# 3V3.net
KiCad netlist of a schematic drawn in Altium Designer
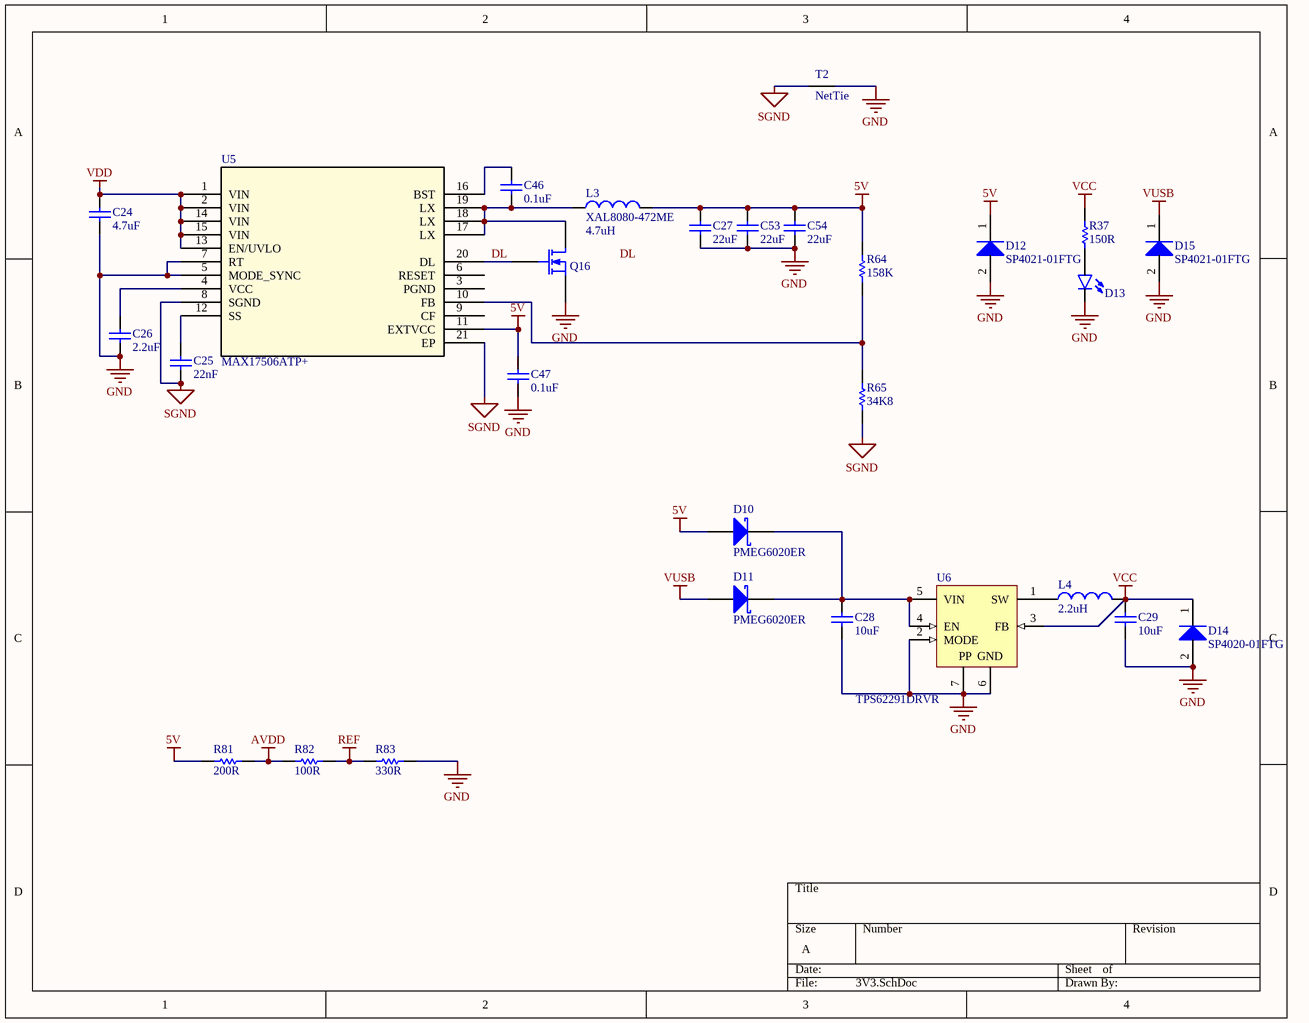
[diagram p0: 3V3.SchDoc]

(export (version "E")
  (design (tool "Eeschema 10.0.6"))
  (components
    (comp (ref "C24")
      (value "4.7uF")
      (footprint "C1210[3225X200]")
      (description "4.7uF 100V 10% 1210 (3225 Metric)")
      (fields (field (name "PARTNUMBER") "GRJ32DC72A475KE11L") (field (name "MANUFACTURER") "Murata"))
      (libsource (lib "Capacitors") (part "CAP_4.7uF_100V_1210_10%"))
    )
    (comp (ref "C25")
      (value "22nF")
      (footprint "C0603[1608X92]")
      (description "22nF 50V 10% 0603 (1608 Metric)")
      (fields (field (name "PARTNUMBER") "GRM188R71H223KA01D") (field (name "MANUFACTURER") "Murata"))
      (libsource (lib "Capacitors") (part "CAP_22nF_50V_0603_10%"))
    )
    (comp (ref "C26")
      (value "2.2uF")
      (footprint "C0603[1608X92]")
      (description "2.2uF 10V 10% 0603 (1608 Metric)")
      (fields (field (name "PARTNUMBER") "GRT188R61A225KE13D") (field (name "MANUFACTURER") "Murata"))
      (libsource (lib "Capacitors") (part "CAP_2.2uF_10V_0603_10%"))
    )
    (comp (ref "C27")
      (value "22uF")
      (footprint "C1210[3225X250]")
      (description "22uF 16V 20% 1210 (3225 Metric)")
      (fields (field (name "PARTNUMBER") "GRM32ER61C476ME15L") (field (name "MANUFACTURER") "Murata"))
      (libsource (lib "Capacitors") (part "CAP_22uF_16V_1210_20%_1"))
    )
    (comp (ref "C28")
      (value "10uF")
      (footprint "C0603[1608X92]")
      (description "10uF 16V 10% 0603 (1608 Metric)")
      (fields (field (name "PARTNUMBER") "GRM188R61C106KAALD") (field (name "MANUFACTURER") "Murata"))
      (libsource (lib "Capacitors") (part "CAP_10uF_16V_0603_10%"))
    )
    (comp (ref "C29")
      (value "10uF")
      (footprint "C0603[1608X92]")
      (description "10uF 6.3V 10% 0603 (1608 Metric)")
      (fields (field (name "PARTNUMBER") "GRM188R60J106KE47D") (field (name "MANUFACTURER") "Murata"))
      (libsource (lib "Capacitors") (part "CAP_10uF_6.3V_0603_10%"))
    )
    (comp (ref "C46")
      (value "0.1uF")
      (footprint "C0603[1608X92]")
      (description "0.1uF 16V 10% 0603 (1608 Metric)")
      (fields (field (name "PARTNUMBER") "GCM188R71C104KA37D") (field (name "MANUFACTURER") "Murata"))
      (libsource (lib "Capacitors") (part "CAP_0.1uF_16V_0603_10%"))
    )
    (comp (ref "C47")
      (value "0.1uF")
      (footprint "C0603[1608X92]")
      (description "0.1uF 6.3V 10% 0603 (1608 Metric)")
      (fields (field (name "PARTNUMBER") "GRM188R70J104KA01D") (field (name "MANUFACTURER") "Murata"))
      (libsource (lib "Capacitors") (part "CAP_0.1uF_6.3V_0603_10%"))
    )
    (comp (ref "C53")
      (value "22uF")
      (footprint "C1210[3225X250]")
      (description "22uF 16V 20% 1210 (3225 Metric)")
      (fields (field (name "PARTNUMBER") "GRM32ER61C476ME15L") (field (name "MANUFACTURER") "Murata"))
      (libsource (lib "Capacitors") (part "CAP_22uF_16V_1210_20%_1"))
    )
    (comp (ref "C54")
      (value "22uF")
      (footprint "C1210[3225X250]")
      (description "22uF 16V 20% 1210 (3225 Metric)")
      (fields (field (name "PARTNUMBER") "GRM32ER61C476ME15L") (field (name "MANUFACTURER") "Murata"))
      (libsource (lib "Capacitors") (part "CAP_22uF_16V_1210_20%_1"))
    )
    (comp (ref "D10")
      (value "PMEG6020ER")
      (footprint "SOD-123")
      (fields (field (name "PARTNUMBER") "PMEG6020ER,115") (field (name "MANUFACTURER") "NXP Semiconductors"))
      (libsource (lib "Diodes") (part "PMEG6020ER"))
    )
    (comp (ref "D11")
      (value "PMEG6020ER")
      (footprint "SOD-123")
      (fields (field (name "PARTNUMBER") "PMEG6020ER,115") (field (name "MANUFACTURER") "NXP Semiconductors"))
      (libsource (lib "Diodes") (part "PMEG6020ER"))
    )
    (comp (ref "D12")
      (value "SP4021-01FTG")
      (footprint "SOD-323")
      (fields (field (name "MANUFACTURER") "Littelfuse"))
      (libsource (lib "Diodes") (part "SP4021-01FTG"))
    )
    (comp (ref "D13")
      (value "LED_0603_GREEN_5mA")
      (footprint "LED0603")
      (fields (field (name "PARTNUMBER") "LTST-C193TGKT-5A") (field (name "MANUFACTURER") "Lite-On Inc."))
      (libsource (lib "LEDs") (part "LED_0603_GREEN_5mA"))
    )
    (comp (ref "D14")
      (value "SP4020-01FTG")
      (footprint "SOD-323")
      (fields (field (name "MANUFACTURER") "Littelfuse"))
      (libsource (lib "Diodes") (part "SP4020-01FTG"))
    )
    (comp (ref "D15")
      (value "SP4021-01FTG")
      (footprint "SOD-323")
      (fields (field (name "MANUFACTURER") "Littelfuse"))
      (libsource (lib "Diodes-TVS") (part "SP4021-01FTG"))
    )
    (comp (ref "L3")
      (value "XAL8080-472ME")
      (footprint "XAL8080")
      (description "4.7uH 38A 4.08mOhms")
      (fields
        (field (name "ALTIUM_VALUE") "4.7uH")
        (field (name "PARTNUMBER") "XAL8080-472MED")
        (field (name "MANUFACTURER") "Coilcraft")
        (field (name "PUBLISHER") "Altium Limited")
      )
      (libsource (lib "General_Component") (part "XAL8080-472ME"))
    )
    (comp (ref "L4")
      (value "2.2uH")
      (footprint "IND0805")
      (description "2.2uH 20% 1.7A 0805")
      (fields (field (name "PARTNUMBER") "LQM21PN2R2MGHL") (field (name "MANUFACTURER") "Murata"))
      (libsource (lib "Inductors") (part "IND_2.2uH_1.7A_0805_20%"))
    )
    (comp (ref "Q16")
      (value "SIS862DN-T1-GE3")
      (footprint "PowerPak-1212-8")
      (description "N-Channel MOSFET")
      (fields (field (name "MANUFACTURER") "Vishay"))
      (libsource (lib "MOSFETs") (part "SIS862DN-T1-GE3"))
    )
    (comp (ref "R37")
      (value "150R")
      (footprint "R0603[1608]")
      (description "150R 0.25W 1% 0603 (1005 Metric)")
      (fields (field (name "MANUFACTURER") "Vishay / Dale") (field (name "PARTNUMBER") "CRCW0603150RFKEAHP"))
      (libsource (lib "Resistors") (part "RES_150R_0603_1%"))
    )
    (comp (ref "R64")
      (value "158K")
      (footprint "R0603[1608]")
      (description "158K 0.25W 1% 0603 (1005 Metric)")
      (fields (field (name "MANUFACTURER") "Vishay / Dale") (field (name "PARTNUMBER") "CRCW0603158KFKEAHP"))
      (libsource (lib "Resistors") (part "RES_158K_0603_1%"))
    )
    (comp (ref "R65")
      (value "34K8")
      (footprint "R0603[1608]")
      (description "34K8 0.25W 1% 0603 (1005 Metric)")
      (fields (field (name "MANUFACTURER") "Vishay / Dale") (field (name "PARTNUMBER") "CRCW060334K8FKEAHP"))
      (libsource (lib "Resistors") (part "RES_34K8_0603_1%"))
    )
    (comp (ref "R81")
      (value "200R")
      (footprint "R0603[1608]")
      (description "200R 0.25W 1% 0603 (1005 Metric)")
      (fields (field (name "MANUFACTURER") "Vishay / Dale") (field (name "PARTNUMBER") "CRCW0603200RFKEAHP"))
      (libsource (lib "Resistors") (part "RES_200R_0603_1%"))
    )
    (comp (ref "R82")
      (value "100R")
      (footprint "R0603[1608]")
      (description "100R 0.25W 1% 0603 (1005 Metric)")
      (fields (field (name "MANUFACTURER") "Vishay / Dale") (field (name "PARTNUMBER") "CRCW0603100RFKEAHP"))
      (libsource (lib "Resistors") (part "RES_100R_0603_1%"))
    )
    (comp (ref "R83")
      (value "330R")
      (footprint "R0603[1608]")
      (description "330R 0.25W 1% 0603 (1005 Metric)")
      (fields (field (name "MANUFACTURER") "Vishay / Dale") (field (name "PARTNUMBER") "CRCW0603330RFKEAHP"))
      (libsource (lib "Resistors") (part "RES_330R_0603_1%"))
    )
    (comp (ref "T2") (value "NetTie") (footprint "NetTie") (libsource (lib "Components") (part "NetTie")))
    (comp (ref "U5")
      (value "MAX17506ATP+")
      (footprint "21-0140L_T2055-4")
      (fields (field (name "MANUFACTURER") "Maxim"))
      (libsource (lib "General_Component") (part "MAX17506ATP+"))
    )
    (comp (ref "U6")
      (value "TPS62291DRVR")
      (footprint "WSON-6")
      (description "Voltage Regulators - Switching Regulators 2.25MHz 1A Step-Down Cnvrtr 3.3V Output")
      (fields (field (name "MANUFACTURER") "Texas Instruments"))
      (libsource (lib "ICs") (part "TPS62291DRVR"))
    )
  )
  (nets
    (net (code "1") (name "/DL") (class "Default")
      (node (ref "Q16") (pin "2") (pinfunction "G_2") (pintype "passive"))
      (node (ref "U5") (pin "20") (pinfunction "DL_20") (pintype "passive"))
    )
    (net (code "2") (name "5V") (class "Default")
      (node (ref "C27") (pin "2") (pinfunction "2_2") (pintype "passive"))
      (node (ref "C47") (pin "2") (pinfunction "2_2") (pintype "passive"))
      (node (ref "C53") (pin "2") (pinfunction "2_2") (pintype "passive"))
      (node (ref "C54") (pin "2") (pinfunction "2_2") (pintype "passive"))
      (node (ref "D10") (pin "2") (pinfunction "A_2") (pintype "passive"))
      (node (ref "D12") (pin "1") (pinfunction "K_1") (pintype "passive"))
      (node (ref "L3") (pin "2") (pinfunction "2_2") (pintype "passive"))
      (node (ref "R64") (pin "2") (pinfunction "2_2") (pintype "passive"))
      (node (ref "R81") (pin "1") (pinfunction "1_1") (pintype "passive"))
      (node (ref "U5") (pin "11") (pinfunction "EXTVCC_11") (pintype "passive"))
    )
    (net (code "3") (name "AVDD") (class "Default")
      (node (ref "R81") (pin "2") (pinfunction "2_2") (pintype "passive"))
      (node (ref "R82") (pin "1") (pinfunction "1_1") (pintype "passive"))
    )
    (net (code "4") (name "GND") (class "Default")
      (node (ref "C24") (pin "1") (pinfunction "1_1") (pintype "passive"))
      (node (ref "C26") (pin "1") (pinfunction "1_1") (pintype "passive"))
      (node (ref "C27") (pin "1") (pinfunction "1_1") (pintype "passive"))
      (node (ref "C28") (pin "1") (pinfunction "1_1") (pintype "passive"))
      (node (ref "C29") (pin "1") (pinfunction "1_1") (pintype "passive"))
      (node (ref "C47") (pin "1") (pinfunction "1_1") (pintype "passive"))
      (node (ref "C53") (pin "1") (pinfunction "1_1") (pintype "passive"))
      (node (ref "C54") (pin "1") (pinfunction "1_1") (pintype "passive"))
      (node (ref "D12") (pin "2") (pinfunction "A_2") (pintype "passive"))
      (node (ref "D13") (pin "C") (pinfunction "C_C") (pintype "passive"))
      (node (ref "D14") (pin "2") (pinfunction "A_2") (pintype "passive"))
      (node (ref "D15") (pin "2") (pinfunction "A_2") (pintype "passive"))
      (node (ref "Q16") (pin "1") (pinfunction "S_1") (pintype "passive"))
      (node (ref "R83") (pin "2") (pinfunction "2_2") (pintype "passive"))
      (node (ref "T2") (pin "2") (pinfunction "2_2") (pintype "passive"))
      (node (ref "U5") (pin "5") (pinfunction "MODE_SYNC_5") (pintype "passive"))
      (node (ref "U5") (pin "7") (pinfunction "RT_7") (pintype "passive"))
      (node (ref "U6") (pin "2") (pinfunction "MODE_2") (pintype "input"))
      (node (ref "U6") (pin "6") (pinfunction "GND_6") (pintype "power_in"))
      (node (ref "U6") (pin "7") (pinfunction "EP_7") (pintype "passive"))
    )
    (net (code "5") (name "Net-(D10-K)") (class "Default")
      (node (ref "C28") (pin "2") (pinfunction "2_2") (pintype "passive"))
      (node (ref "D10") (pin "1") (pinfunction "K_1") (pintype "passive"))
      (node (ref "D11") (pin "1") (pinfunction "K_1") (pintype "passive"))
      (node (ref "U6") (pin "4") (pinfunction "EN_4") (pintype "input"))
      (node (ref "U6") (pin "5") (pinfunction "VIN_5") (pintype "power_in"))
    )
    (net (code "6") (name "Net-(D13-PadA)") (class "Default")
      (node (ref "D13") (pin "A") (pinfunction "A_A") (pintype "passive"))
      (node (ref "R37") (pin "1") (pinfunction "1_1") (pintype "passive"))
    )
    (net (code "7") (name "Net-(Q16-D)") (class "Default")
      (node (ref "C46") (pin "1") (pinfunction "1_1") (pintype "passive"))
      (node (ref "L3") (pin "1") (pinfunction "1_1") (pintype "passive"))
      (node (ref "Q16") (pin "3") (pinfunction "D_3") (pintype "passive"))
      (node (ref "U5") (pin "17") (pinfunction "LX_17") (pintype "passive"))
      (node (ref "U5") (pin "18") (pinfunction "LX_18") (pintype "passive"))
      (node (ref "U5") (pin "19") (pinfunction "LX_19") (pintype "passive"))
    )
    (net (code "8") (name "Net-(U5-BST)") (class "Default")
      (node (ref "C46") (pin "2") (pinfunction "2_2") (pintype "passive"))
      (node (ref "U5") (pin "16") (pinfunction "BST_16") (pintype "passive"))
    )
    (net (code "9") (name "Net-(U5-FB)") (class "Default")
      (node (ref "R64") (pin "1") (pinfunction "1_1") (pintype "passive"))
      (node (ref "R65") (pin "2") (pinfunction "2_2") (pintype "passive"))
      (node (ref "U5") (pin "10") (pinfunction "FB_10") (pintype "passive"))
    )
    (net (code "10") (name "Net-(U5-SS)") (class "Default")
      (node (ref "C25") (pin "2") (pinfunction "2_2") (pintype "passive"))
      (node (ref "U5") (pin "12") (pinfunction "SS_12") (pintype "passive"))
    )
    (net (code "11") (name "Net-(U5-VCC)") (class "Default")
      (node (ref "C26") (pin "2") (pinfunction "2_2") (pintype "passive"))
      (node (ref "U5") (pin "4") (pinfunction "VCC_4") (pintype "power_in"))
    )
    (net (code "12") (name "Net-(U6-SW)") (class "Default")
      (node (ref "L4") (pin "1") (pinfunction "1_1") (pintype "passive"))
      (node (ref "U6") (pin "1") (pinfunction "SW_1") (pintype "power_in"))
    )
    (net (code "13") (name "REF") (class "Default")
      (node (ref "R82") (pin "2") (pinfunction "2_2") (pintype "passive"))
      (node (ref "R83") (pin "1") (pinfunction "1_1") (pintype "passive"))
    )
    (net (code "14") (name "SGND") (class "Default")
      (node (ref "C25") (pin "1") (pinfunction "1_1") (pintype "passive"))
      (node (ref "R65") (pin "1") (pinfunction "1_1") (pintype "passive"))
      (node (ref "T2") (pin "1") (pinfunction "1_1") (pintype "passive"))
      (node (ref "U5") (pin "21") (pinfunction "EP_21") (pintype "passive"))
      (node (ref "U5") (pin "8") (pinfunction "SGND_8") (pintype "power_in"))
    )
    (net (code "15") (name "VCC") (class "Default")
      (node (ref "C29") (pin "2") (pinfunction "2_2") (pintype "passive"))
      (node (ref "D14") (pin "1") (pinfunction "K_1") (pintype "passive"))
      (node (ref "L4") (pin "2") (pinfunction "2_2") (pintype "passive"))
      (node (ref "R37") (pin "2") (pinfunction "2_2") (pintype "passive"))
      (node (ref "U6") (pin "3") (pinfunction "FB_3") (pintype "input"))
    )
    (net (code "16") (name "VDD") (class "Default")
      (node (ref "C24") (pin "2") (pinfunction "2_2") (pintype "passive"))
      (node (ref "U5") (pin "1") (pinfunction "VIN_1") (pintype "passive"))
      (node (ref "U5") (pin "13") (pinfunction "EN/UVLO_13") (pintype "passive"))
      (node (ref "U5") (pin "14") (pinfunction "VIN_14") (pintype "passive"))
      (node (ref "U5") (pin "15") (pinfunction "VIN_15") (pintype "passive"))
      (node (ref "U5") (pin "2") (pinfunction "VIN_2") (pintype "passive"))
    )
    (net (code "17") (name "VUSB") (class "Default")
      (node (ref "D11") (pin "2") (pinfunction "A_2") (pintype "passive"))
      (node (ref "D15") (pin "1") (pinfunction "K_1") (pintype "passive"))
    )
    (net (code "18") (name "unconnected-(U5-CF-Pad9)") (class "Default")
      (node (ref "U5") (pin "9") (pinfunction "CF_9") (pintype "passive"))
    )
    (net (code "19") (name "unconnected-(U5-PGND-Pad3)") (class "Default")
      (node (ref "U5") (pin "3") (pinfunction "PGND_3") (pintype "passive"))
    )
    (net (code "20") (name "unconnected-(U5-RESET-Pad6)") (class "Default")
      (node (ref "U5") (pin "6") (pinfunction "RESET_6") (pintype "passive"))
    )
  )
)
